# MicroSD.net
KiCad netlist of a schematic drawn in Altium Designer
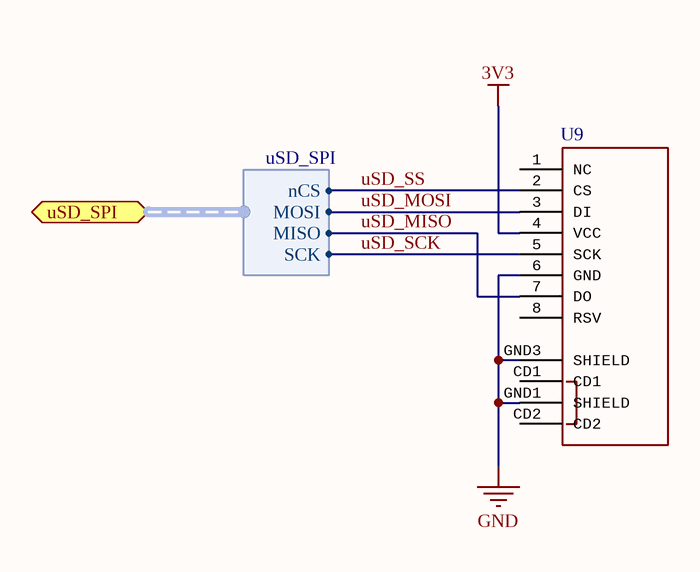
[diagram p0: MicroSD.SchDoc]

(export (version "E")
  (design (tool "Eeschema 10.0.6"))
  (components
    (comp (ref "U9")
      (value "microSD Socket")
      (footprint "MICRO-SD-SOCKET-PP")
      (libsource (lib "SparkFun-Connectors") (part "USD-SOCKETNEW"))
    )
  )
  (nets
    (net (code "2") (name "/uSD_MISO") (class "Default")
      (node (ref "U9") (pin "7") (pinfunction "DO_7") (pintype "passive"))
    )
    (net (code "3") (name "/uSD_MOSI") (class "Default")
      (node (ref "U9") (pin "3") (pinfunction "DI_3") (pintype "passive"))
    )
    (net (code "4") (name "/uSD_SCK") (class "Default")
      (node (ref "U9") (pin "5") (pinfunction "SCK_5") (pintype "passive"))
    )
    (net (code "5") (name "/uSD_SS") (class "Default")
      (node (ref "U9") (pin "2") (pinfunction "CS_2") (pintype "passive"))
    )
    (net (code "7") (name "3V3") (class "Default")
      (node (ref "U9") (pin "4") (pinfunction "VCC_4") (pintype "passive"))
    )
    (net (code "8") (name "GND") (class "Default")
      (node (ref "U9") (pin "6") (pinfunction "GND_6") (pintype "passive"))
      (node (ref "U9") (pin "GND1") (pinfunction "SHIELD_GND1") (pintype "passive"))
      (node (ref "U9") (pin "GND3") (pinfunction "SHIELD_GND3") (pintype "passive"))
    )
    (net (code "9") (name "unconnected-(U9-NC-Pad1)") (class "Default")
      (node (ref "U9") (pin "1") (pinfunction "NC_1") (pintype "passive"))
    )
    (net (code "10") (name "unconnected-(U9-PadCD1)") (class "Default")
      (node (ref "U9") (pin "CD1") (pinfunction "CD1_CD1") (pintype "passive"))
    )
    (net (code "11") (name "unconnected-(U9-PadCD2)") (class "Default")
      (node (ref "U9") (pin "CD2") (pinfunction "CD2_CD2") (pintype "passive"))
    )
    (net (code "12") (name "unconnected-(U9-RSV-Pad8)") (class "Default")
      (node (ref "U9") (pin "8") (pinfunction "RSV_8") (pintype "passive"))
    )
  )
)
